# max86141-breakout.net
KiCad netlist of a schematic drawn in EAGLE
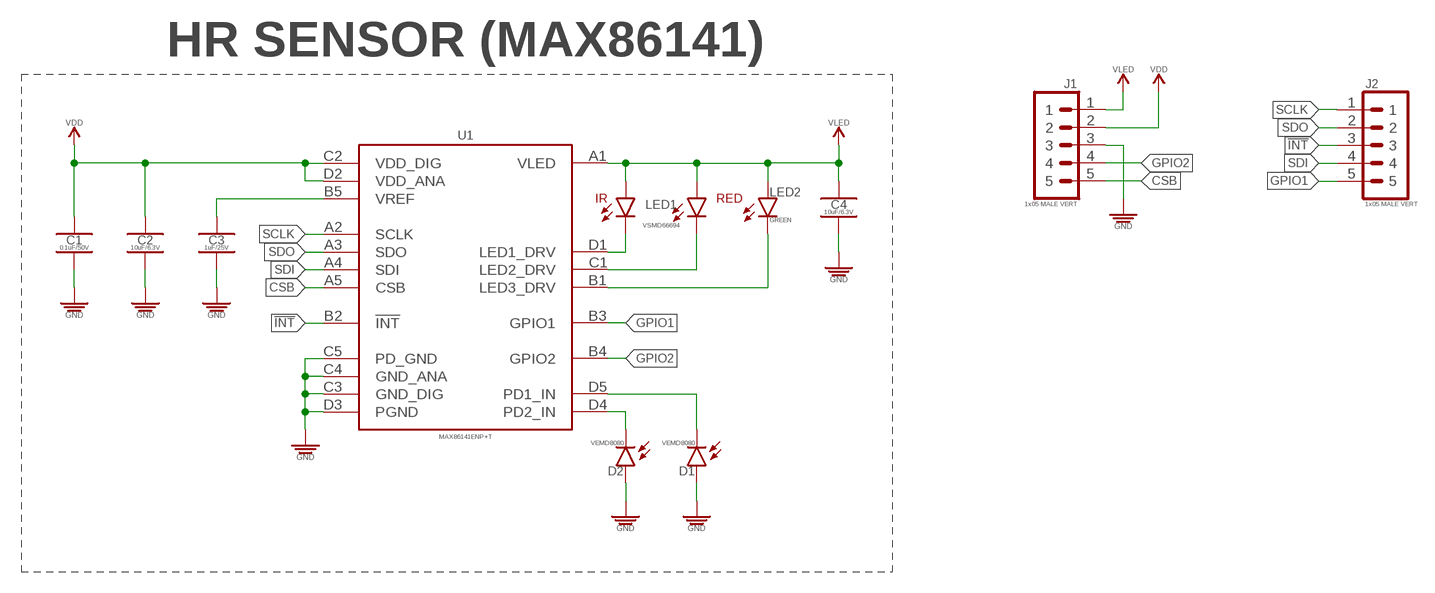
[diagram p0: schematic, sheet 1]

(export (version "E")
  (design (tool "Eeschema 10.0.6"))
  (components
    (comp (ref "C1")
      (value "0.1uF/50V")
      (footprint "eagle-import:CAPC1005X55_SMD-0402")
      (fields (field (name "MFR") "TDK Corporation") (field (name "MPN") "C1005X7R1H104K050BE"))
      (libsource (lib "eagle-import") (part "0.1UF_SMD-0402_50V-10%"))
    )
    (comp (ref "C2")
      (value "10uF/6.3V")
      (footprint "eagle-import:CAPC1005X55_SMD-0402")
      (fields
        (field (name "MFR") "Murata Electronics North America")
        (field (name "MPN") "GRM155C80J106ME11D")
      )
      (libsource (lib "eagle-import") (part "10UF_CER_SMD-0402_6.3V-20%"))
    )
    (comp (ref "C3")
      (value "1uF/25V")
      (footprint "eagle-import:CAPC1005X55_SMD-0402")
      (fields (field (name "MFR") "TDK Corporation") (field (name "MPN") "CGB2A1X5R1E105K033BC"))
      (libsource (lib "eagle-import") (part "1UF_CER_SMD-0402_25V-10%"))
    )
    (comp (ref "C4")
      (value "10uF/6.3V")
      (footprint "eagle-import:CAPC1005X55_SMD-0402")
      (fields
        (field (name "MFR") "Murata Electronics North America")
        (field (name "MPN") "GRM155C80J106ME11D")
      )
      (libsource (lib "eagle-import") (part "10UF_CER_SMD-0402_6.3V-20%"))
    )
    (comp (ref "D1")
      (value "VEMD8080")
      (footprint "eagle-import:SON131P250X480X53-8N")
      (fields (field (name "MFR") "Vishay Semiconductor Opto Division"))
      (libsource (lib "eagle-import") (part "VEMD8080"))
    )
    (comp (ref "D2")
      (value "VEMD8080")
      (footprint "eagle-import:SON131P250X480X53-8N")
      (fields (field (name "MFR") "Vishay Semiconductor Opto Division"))
      (libsource (lib "eagle-import") (part "VEMD8080"))
    )
    (comp (ref "J1")
      (value "1x05 MALE VERT")
      (footprint "eagle-import:HDRV5W64P254_1X5_1270X254X838B")
      (fields (field (name "MFR") "Sullins Connector Solutions") (field (name "MPN") "PEC05SAAN"))
      (libsource (lib "eagle-import") (part "1X05_PTH_VERT_MALE_2.54MM"))
    )
    (comp (ref "J2")
      (value "1x05 MALE VERT")
      (footprint "eagle-import:HDRV5W64P254_1X5_1270X254X838B")
      (fields (field (name "MFR") "Sullins Connector Solutions") (field (name "MPN") "PEC05SAAN"))
      (libsource (lib "eagle-import") (part "1X05_PTH_VERT_MALE_2.54MM"))
    )
    (comp (ref "LED1")
      (value "VSMD66694")
      (footprint "eagle-import:DIOCAV100P200X200X87-4N")
      (fields (field (name "MFR") "Vishay Semiconductor Opto Division"))
      (libsource (lib "eagle-import") (part "VSMD66694"))
    )
    (comp (ref "LED2")
      (value "GREEN")
      (footprint "eagle-import:LEDC1005X40_LED-0402")
      (fields (field (name "MFR") "Bivar Inc.") (field (name "MPN") "SM0402GC"))
      (libsource (lib "eagle-import") (part "LED_SMD-0402_DISCRETE_GREEN"))
    )
    (comp (ref "U1")
      (value "MAX86141ENP+T")
      (footprint "eagle-import:BGA20C40P5X4_184X204X100N")
      (fields (field (name "MFR") "Maxim Integrated"))
      (libsource (lib "eagle-import") (part "MAX86141"))
    )
  )
  (nets
    (net (code "1") (name "/~{INT}") (class "Default")
      (node (ref "J2") (pin "3") (pinfunction "3_3") (pintype "passive"))
      (node (ref "U1") (pin "B2") (pinfunction "~{INT}_B2") (pintype "bidirectional"))
    )
    (net (code "2") (name "CSB") (class "Default")
      (node (ref "J1") (pin "5") (pinfunction "5_5") (pintype "passive"))
      (node (ref "U1") (pin "A5") (pinfunction "CSB_A5") (pintype "bidirectional"))
    )
    (net (code "3") (name "GND") (class "Default")
      (node (ref "C1") (pin "2") (pinfunction "2_2") (pintype "passive"))
      (node (ref "C2") (pin "2") (pinfunction "2_2") (pintype "passive"))
      (node (ref "C3") (pin "2") (pinfunction "2_2") (pintype "passive"))
      (node (ref "C4") (pin "2") (pinfunction "2_2") (pintype "passive"))
      (node (ref "D1") (pin "1") (pinfunction "A_1") (pintype "passive"))
      (node (ref "D1") (pin "2") (pinfunction "A_2") (pintype "passive"))
      (node (ref "D1") (pin "3") (pinfunction "A_3") (pintype "passive"))
      (node (ref "D1") (pin "4") (pinfunction "A_4") (pintype "passive"))
      (node (ref "D1") (pin "5") (pinfunction "A_5") (pintype "passive"))
      (node (ref "D1") (pin "6") (pinfunction "A_6") (pintype "passive"))
      (node (ref "D1") (pin "7") (pinfunction "A_7") (pintype "passive"))
      (node (ref "D2") (pin "1") (pinfunction "A_1") (pintype "passive"))
      (node (ref "D2") (pin "2") (pinfunction "A_2") (pintype "passive"))
      (node (ref "D2") (pin "3") (pinfunction "A_3") (pintype "passive"))
      (node (ref "D2") (pin "4") (pinfunction "A_4") (pintype "passive"))
      (node (ref "D2") (pin "5") (pinfunction "A_5") (pintype "passive"))
      (node (ref "D2") (pin "6") (pinfunction "A_6") (pintype "passive"))
      (node (ref "D2") (pin "7") (pinfunction "A_7") (pintype "passive"))
      (node (ref "J1") (pin "3") (pinfunction "3_3") (pintype "passive"))
      (node (ref "U1") (pin "C3") (pinfunction "GND_DIG_C3") (pintype "power_in"))
      (node (ref "U1") (pin "C4") (pinfunction "GND_ANA_C4") (pintype "power_in"))
      (node (ref "U1") (pin "C5") (pinfunction "PD_GND_C5") (pintype "power_in"))
      (node (ref "U1") (pin "D3") (pinfunction "PGND_D3") (pintype "power_in"))
    )
    (net (code "4") (name "GPIO1") (class "Default")
      (node (ref "J2") (pin "5") (pinfunction "5_5") (pintype "passive"))
      (node (ref "U1") (pin "B3") (pinfunction "GPIO1_B3") (pintype "bidirectional"))
    )
    (net (code "5") (name "GPIO2") (class "Default")
      (node (ref "J1") (pin "4") (pinfunction "4_4") (pintype "passive"))
      (node (ref "U1") (pin "B4") (pinfunction "GPIO2_B4") (pintype "bidirectional"))
    )
    (net (code "6") (name "Net-(D1-K)") (class "Default")
      (node (ref "D1") (pin "8") (pinfunction "K_8") (pintype "passive"))
      (node (ref "U1") (pin "D5") (pinfunction "PD1_IN_D5") (pintype "bidirectional"))
    )
    (net (code "7") (name "Net-(D2-K)") (class "Default")
      (node (ref "D2") (pin "8") (pinfunction "K_8") (pintype "passive"))
      (node (ref "U1") (pin "D4") (pinfunction "PD2_IN_D4") (pintype "bidirectional"))
    )
    (net (code "8") (name "Net-(LED1-K-IR)") (class "Default")
      (node (ref "LED1") (pin "1") (pinfunction "K-IR_1") (pintype "passive"))
      (node (ref "U1") (pin "D1") (pinfunction "LED1_DRV_D1") (pintype "bidirectional"))
    )
    (net (code "9") (name "Net-(LED1-K-RED)") (class "Default")
      (node (ref "LED1") (pin "3") (pinfunction "K-RED_3") (pintype "passive"))
      (node (ref "U1") (pin "C1") (pinfunction "LED2_DRV_C1") (pintype "bidirectional"))
    )
    (net (code "10") (name "Net-(U1-LED3_DRV)") (class "Default")
      (node (ref "LED2") (pin "K") (pinfunction "K_K") (pintype "passive"))
      (node (ref "U1") (pin "B1") (pinfunction "LED3_DRV_B1") (pintype "bidirectional"))
    )
    (net (code "11") (name "Net-(U1-VREF)") (class "Default")
      (node (ref "C3") (pin "1") (pinfunction "1_1") (pintype "passive"))
      (node (ref "U1") (pin "B5") (pinfunction "VREF_B5") (pintype "power_in"))
    )
    (net (code "12") (name "SCLK") (class "Default")
      (node (ref "J2") (pin "1") (pinfunction "1_1") (pintype "passive"))
      (node (ref "U1") (pin "A2") (pinfunction "SCLK_A2") (pintype "bidirectional"))
    )
    (net (code "13") (name "SDI") (class "Default")
      (node (ref "J2") (pin "4") (pinfunction "4_4") (pintype "passive"))
      (node (ref "U1") (pin "A4") (pinfunction "SDI_A4") (pintype "bidirectional"))
    )
    (net (code "14") (name "SDO") (class "Default")
      (node (ref "J2") (pin "2") (pinfunction "2_2") (pintype "passive"))
      (node (ref "U1") (pin "A3") (pinfunction "SDO_A3") (pintype "bidirectional"))
    )
    (net (code "15") (name "VDD") (class "Default")
      (node (ref "C1") (pin "1") (pinfunction "1_1") (pintype "passive"))
      (node (ref "C2") (pin "1") (pinfunction "1_1") (pintype "passive"))
      (node (ref "J1") (pin "2") (pinfunction "2_2") (pintype "passive"))
      (node (ref "U1") (pin "C2") (pinfunction "VDD_DIG_C2") (pintype "power_in"))
      (node (ref "U1") (pin "D2") (pinfunction "VDD_ANA_D2") (pintype "power_in"))
    )
    (net (code "16") (name "VLED") (class "Default")
      (node (ref "C4") (pin "1") (pinfunction "1_1") (pintype "passive"))
      (node (ref "J1") (pin "1") (pinfunction "1_1") (pintype "passive"))
      (node (ref "LED1") (pin "2") (pinfunction "A-RED_2") (pintype "passive"))
      (node (ref "LED1") (pin "4") (pinfunction "A-IR_4") (pintype "passive"))
      (node (ref "LED2") (pin "A") (pinfunction "A_A") (pintype "passive"))
      (node (ref "U1") (pin "A1") (pinfunction "VLED_A1") (pintype "power_in"))
    )
  )
)
